# V1_Layout.net
KiCad netlist of a schematic drawn in EAGLE
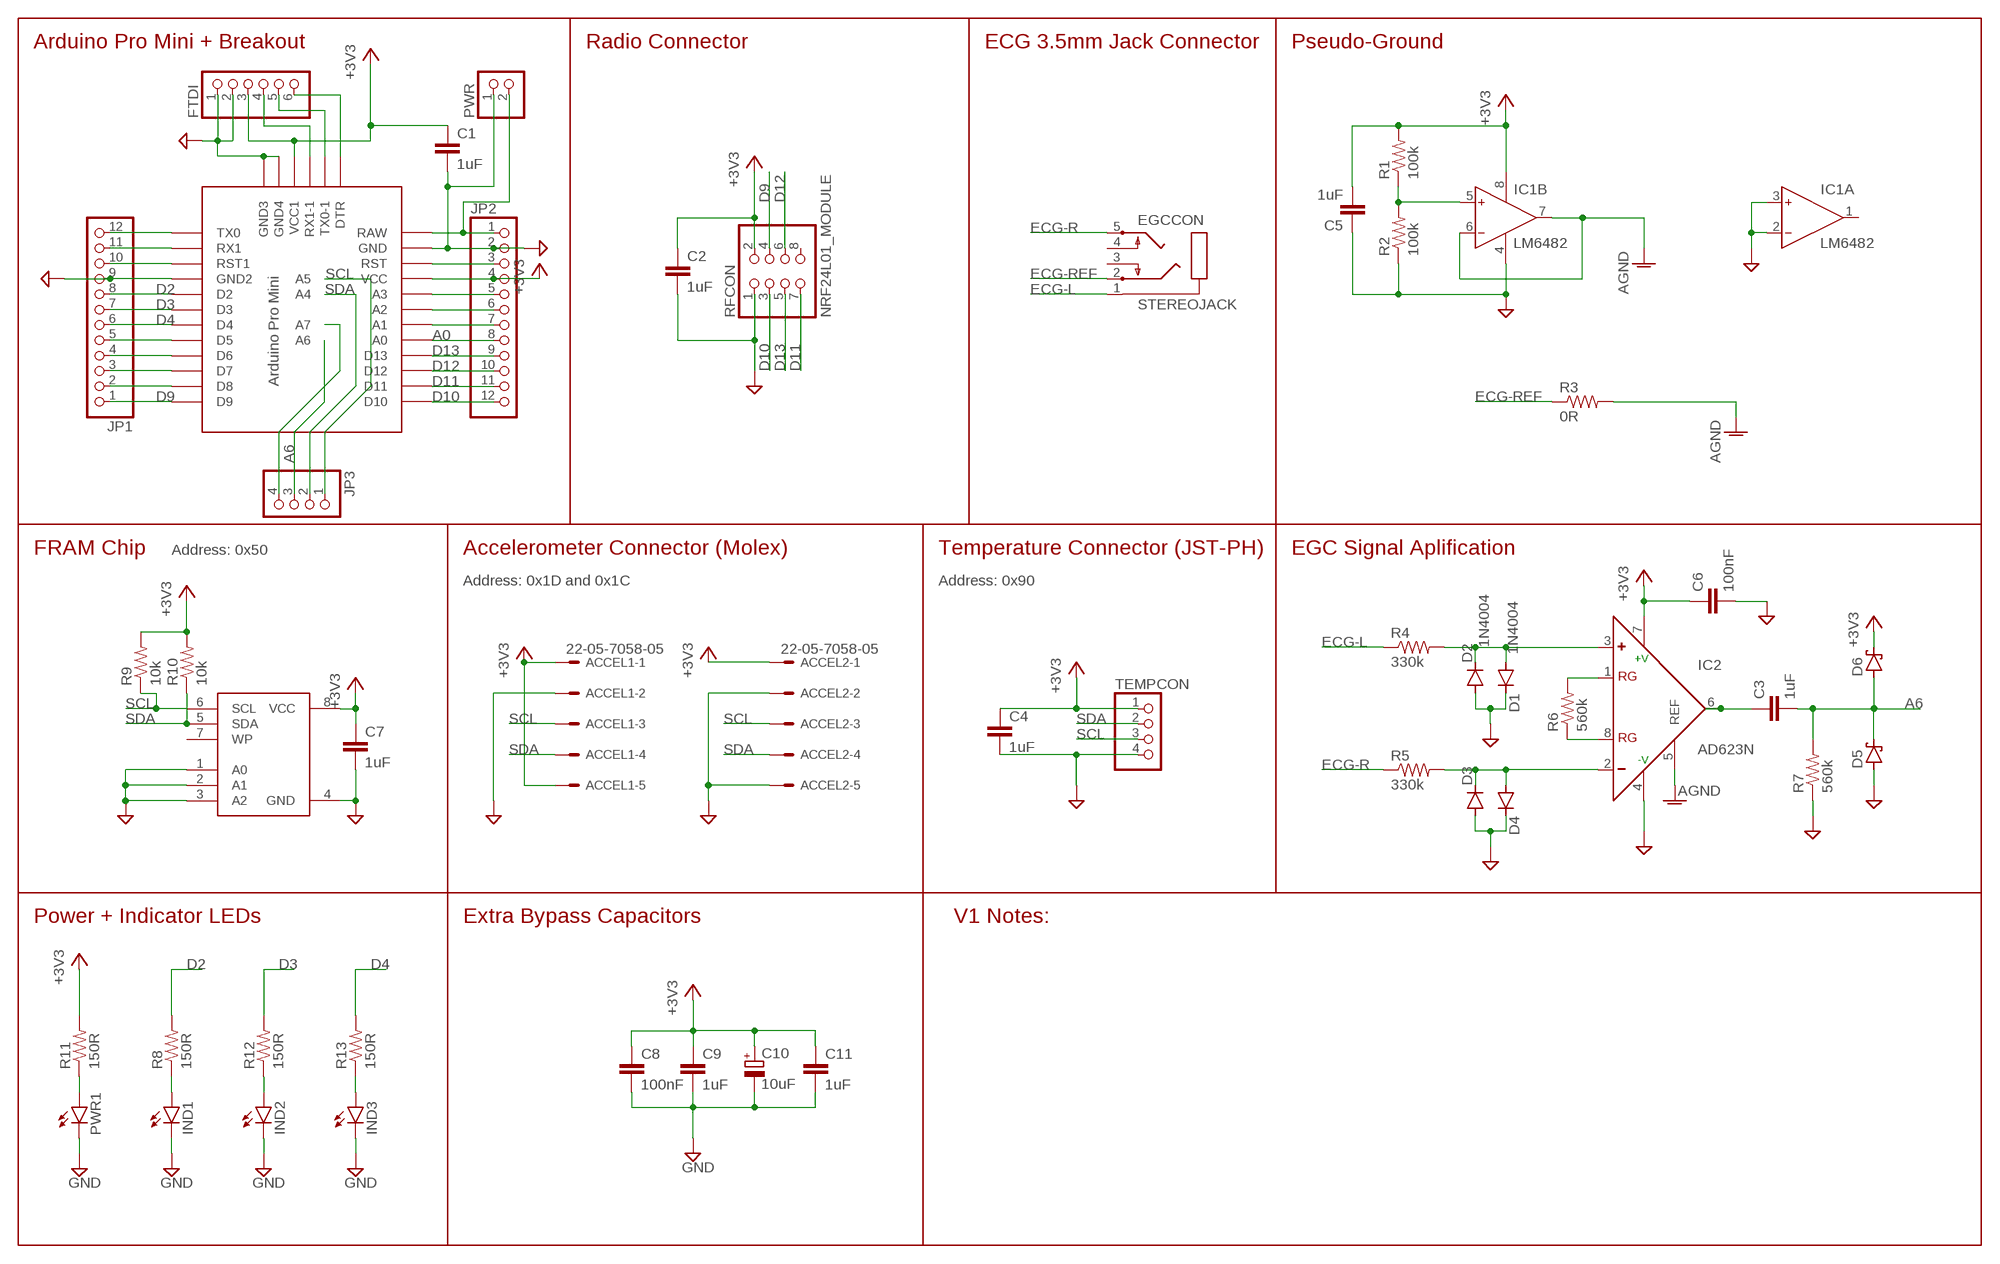
[diagram p0: schematic, sheet 1]

(export (version "E")
  (design (tool "Eeschema 10.0.6"))
  (components
    (comp (ref "ACCEL1")
      (value "22-05-7058-05")
      (footprint "eagle-import:7395-05")
      (fields (field (name "MF") "MOLEX"))
      (libsource (lib "eagle-import") (part "22-?-0505-7058"))
    )
    (comp (ref "ACCEL2")
      (value "22-05-7058-05")
      (footprint "eagle-import:7395-05")
      (fields (field (name "MF") "MOLEX"))
      (libsource (lib "eagle-import") (part "22-?-0505-7058"))
    )
    (comp (ref "C1")
      (value "1uF")
      (footprint "eagle-import:C0603")
      (libsource (lib "eagle-import") (part "C-EUC0603"))
    )
    (comp (ref "C2")
      (value "1uF")
      (footprint "eagle-import:C0603")
      (libsource (lib "eagle-import") (part "C-EUC0603"))
    )
    (comp (ref "C3")
      (value "1uF")
      (footprint "eagle-import:C0603")
      (libsource (lib "eagle-import") (part "C-EUC0603"))
    )
    (comp (ref "C4")
      (value "1uF")
      (footprint "eagle-import:C0603")
      (libsource (lib "eagle-import") (part "C-EUC0603"))
    )
    (comp (ref "C5")
      (value "1uF")
      (footprint "eagle-import:C0603")
      (libsource (lib "eagle-import") (part "C-EUC0603"))
    )
    (comp (ref "C6")
      (value "100nF")
      (footprint "eagle-import:C0603")
      (libsource (lib "eagle-import") (part "C-EUC0603"))
    )
    (comp (ref "C7")
      (value "1uF")
      (footprint "eagle-import:C0603")
      (libsource (lib "eagle-import") (part "C-EUC0603"))
    )
    (comp (ref "C8")
      (value "100nF")
      (footprint "eagle-import:C025-030X050")
      (libsource (lib "eagle-import") (part "C-EU025-030X050"))
    )
    (comp (ref "C9")
      (value "1uF")
      (footprint "eagle-import:C025-030X050")
      (libsource (lib "eagle-import") (part "C-EU025-030X050"))
    )
    (comp (ref "C10")
      (value "10uF")
      (footprint "eagle-import:TAP5-45")
      (libsource (lib "eagle-import") (part "CPOL-EUTAP5-45"))
    )
    (comp (ref "C11")
      (value "1uF")
      (footprint "eagle-import:C025-030X050")
      (libsource (lib "eagle-import") (part "C-EU025-030X050"))
    )
    (comp (ref "D1")
      (value "1N4004")
      (footprint "eagle-import:DO41-10")
      (libsource (lib "eagle-import") (part "1N4004"))
    )
    (comp (ref "D2")
      (value "1N4004")
      (footprint "eagle-import:DO41-10")
      (libsource (lib "eagle-import") (part "1N4004"))
    )
    (comp (ref "D3")
      (value "1N4004")
      (footprint "eagle-import:DO41-10")
      (libsource (lib "eagle-import") (part "1N4004"))
    )
    (comp (ref "D4")
      (value "1N4004")
      (footprint "eagle-import:DO41-10")
      (libsource (lib "eagle-import") (part "1N4004"))
    )
    (comp (ref "D5")
      (value "SCHOTTKY-DIODEDO35-7")
      (footprint "eagle-import:DO35-7")
      (libsource (lib "eagle-import") (part "SCHOTTKY-DIODEDO35-7"))
    )
    (comp (ref "D6")
      (value "SCHOTTKY-DIODEDO35-7")
      (footprint "eagle-import:DO35-7")
      (libsource (lib "eagle-import") (part "SCHOTTKY-DIODEDO35-7"))
    )
    (comp (ref "EGCCON")
      (value "STEREOJACK")
      (footprint "eagle-import:STX3100")
      (libsource (lib "eagle-import") (part "STEREOJACK"))
    )
    (comp (ref "FTDI")
      (value "PINHD-1X6")
      (footprint "eagle-import:1X06")
      (libsource (lib "eagle-import") (part "PINHD-1X6"))
    )
    (comp (ref "IC1")
      (value "LM6482")
      (footprint "eagle-import:DIL08")
      (fields (field (name "MF") "ALTERA CORPORATION") (field (name "MPN") "AD826ANZ"))
      (libsource (lib "eagle-import") (part "AD826N"))
    )
    (comp (ref "IC2")
      (value "AD623N")
      (footprint "eagle-import:DIL08")
      (fields (field (name "MF") "ALTERA CORPORATION") (field (name "MPN") "AD623ANZ"))
      (libsource (lib "eagle-import") (part "AD623N"))
    )
    (comp (ref "IND1")
      (value "LEDCHIPLED_0805")
      (footprint "eagle-import:CHIPLED_0805")
      (libsource (lib "eagle-import") (part "LEDCHIPLED_0805"))
    )
    (comp (ref "IND2")
      (value "LEDCHIPLED_0805")
      (footprint "eagle-import:CHIPLED_0805")
      (libsource (lib "eagle-import") (part "LEDCHIPLED_0805"))
    )
    (comp (ref "IND3")
      (value "LEDCHIPLED_0805")
      (footprint "eagle-import:CHIPLED_0805")
      (libsource (lib "eagle-import") (part "LEDCHIPLED_0805"))
    )
    (comp (ref "JP1")
      (value "PINHD-1X12")
      (footprint "eagle-import:1X12")
      (libsource (lib "eagle-import") (part "PINHD-1X12"))
    )
    (comp (ref "JP2")
      (value "PINHD-1X12")
      (footprint "eagle-import:1X12")
      (libsource (lib "eagle-import") (part "PINHD-1X12"))
    )
    (comp (ref "JP3")
      (value "PINHD-1X4")
      (footprint "eagle-import:1X04")
      (libsource (lib "eagle-import") (part "pinhead_325_PINHD-1X4"))
    )
    (comp (ref "PWR")
      (value "PINHD-1X2")
      (footprint "eagle-import:1X02")
      (libsource (lib "eagle-import") (part "PINHD-1X2"))
    )
    (comp (ref "PWR1")
      (value "LEDCHIPLED_0805")
      (footprint "eagle-import:CHIPLED_0805")
      (libsource (lib "eagle-import") (part "LEDCHIPLED_0805"))
    )
    (comp (ref "R1")
      (value "100k")
      (footprint "eagle-import:R0603")
      (libsource (lib "eagle-import") (part "R-US_R0603"))
    )
    (comp (ref "R2")
      (value "100k")
      (footprint "eagle-import:R0603")
      (libsource (lib "eagle-import") (part "R-US_R0603"))
    )
    (comp (ref "R3")
      (value "0R")
      (footprint "eagle-import:R0603")
      (libsource (lib "eagle-import") (part "R-US_R0603"))
    )
    (comp (ref "R4")
      (value "330k")
      (footprint "eagle-import:R0603")
      (libsource (lib "eagle-import") (part "R-US_R0603"))
    )
    (comp (ref "R5")
      (value "330k")
      (footprint "eagle-import:R0603")
      (libsource (lib "eagle-import") (part "R-US_R0603"))
    )
    (comp (ref "R6")
      (value "560k")
      (footprint "eagle-import:R0603")
      (libsource (lib "eagle-import") (part "R-US_R0603"))
    )
    (comp (ref "R7")
      (value "560k")
      (footprint "eagle-import:R0603")
      (libsource (lib "eagle-import") (part "R-US_R0603"))
    )
    (comp (ref "R8")
      (value "150R")
      (footprint "eagle-import:R0603")
      (libsource (lib "eagle-import") (part "R-US_R0603"))
    )
    (comp (ref "R9")
      (value "10k")
      (footprint "eagle-import:R0603")
      (libsource (lib "eagle-import") (part "R-US_R0603"))
    )
    (comp (ref "R10")
      (value "10k")
      (footprint "eagle-import:R0603")
      (libsource (lib "eagle-import") (part "R-US_R0603"))
    )
    (comp (ref "R11")
      (value "150R")
      (footprint "eagle-import:R0603")
      (libsource (lib "eagle-import") (part "R-US_R0603"))
    )
    (comp (ref "R12")
      (value "150R")
      (footprint "eagle-import:R0603")
      (libsource (lib "eagle-import") (part "R-US_R0603"))
    )
    (comp (ref "R13")
      (value "150R")
      (footprint "eagle-import:R0603")
      (libsource (lib "eagle-import") (part "R-US_R0603"))
    )
    (comp (ref "RFCON")
      (value "NRF24L01_MODULE")
      (footprint "eagle-import:2X04")
      (libsource (lib "eagle-import") (part "NRF24L01_MODULE"))
    )
    (comp (ref "TEMPCON")
      (value "PINHD-1X4M")
      (footprint "eagle-import:1X04M")
      (libsource (lib "eagle-import") (part "PINHD-1X4M"))
    )
    (comp (ref "U$1")
      (value "PRO-MINI-2")
      (footprint "eagle-import:PRO-MINI-2")
      (libsource (lib "eagle-import") (part "PRO-MINI-2"))
    )
    (comp (ref "U2")
      (value "MB85RC256VPF-G-JNERE2")
      (footprint "eagle-import:SOIC8")
      (libsource (lib "eagle-import") (part "MB85RC256VPF-G-JNERE2"))
    )
  )
  (nets
    (net (code "1") (name "+3V3") (class "Default")
      (node (ref "ACCEL1") (pin "1") (pinfunction "S_1") (pintype "passive"))
      (node (ref "ACCEL1") (pin "5") (pinfunction "S_5") (pintype "passive"))
      (node (ref "ACCEL2") (pin "1") (pinfunction "S_1") (pintype "passive"))
      (node (ref "C1") (pin "1") (pinfunction "1_1") (pintype "passive"))
      (node (ref "C10") (pin "+") (pinfunction "+_+") (pintype "passive"))
      (node (ref "C11") (pin "1") (pinfunction "1_1") (pintype "passive"))
      (node (ref "C2") (pin "1") (pinfunction "1_1") (pintype "passive"))
      (node (ref "C4") (pin "1") (pinfunction "1_1") (pintype "passive"))
      (node (ref "C5") (pin "2") (pinfunction "2_2") (pintype "passive"))
      (node (ref "C6") (pin "1") (pinfunction "1_1") (pintype "passive"))
      (node (ref "C7") (pin "1") (pinfunction "1_1") (pintype "passive"))
      (node (ref "C8") (pin "1") (pinfunction "1_1") (pintype "passive"))
      (node (ref "C9") (pin "1") (pinfunction "1_1") (pintype "passive"))
      (node (ref "D6") (pin "C") (pinfunction "C_C") (pintype "passive"))
      (node (ref "FTDI") (pin "3") (pinfunction "3_3") (pintype "passive"))
      (node (ref "IC1") (pin "8") (pinfunction "V+_8") (pintype "power_in"))
      (node (ref "IC2") (pin "7") (pinfunction "+V_7") (pintype "power_in"))
      (node (ref "JP2") (pin "4") (pinfunction "4_4") (pintype "passive"))
      (node (ref "R1") (pin "2") (pinfunction "2_2") (pintype "passive"))
      (node (ref "R10") (pin "2") (pinfunction "2_2") (pintype "passive"))
      (node (ref "R11") (pin "2") (pinfunction "2_2") (pintype "passive"))
      (node (ref "R9") (pin "2") (pinfunction "2_2") (pintype "passive"))
      (node (ref "RFCON") (pin "2") (pinfunction "2_2") (pintype "passive"))
      (node (ref "TEMPCON") (pin "1") (pinfunction "1_1") (pintype "passive"))
      (node (ref "U$1") (pin "VCC") (pinfunction "VCC_VCC") (pintype "bidirectional"))
      (node (ref "U$1") (pin "VCC1") (pinfunction "VCC1_VCC1") (pintype "bidirectional"))
      (node (ref "U2") (pin "8") (pinfunction "VCC_8") (pintype "bidirectional"))
    )
    (net (code "2") (name "/A0") (class "Default")
      (node (ref "JP2") (pin "8") (pinfunction "8_8") (pintype "passive"))
      (node (ref "U$1") (pin "A3") (pinfunction "A0_A3") (pintype "bidirectional"))
    )
    (net (code "3") (name "/A6") (class "Default")
      (node (ref "C3") (pin "2") (pinfunction "2_2") (pintype "passive"))
      (node (ref "D5") (pin "C") (pinfunction "C_C") (pintype "passive"))
      (node (ref "D6") (pin "A") (pinfunction "A_A") (pintype "passive"))
      (node (ref "JP3") (pin "3") (pinfunction "3_3") (pintype "passive"))
      (node (ref "R7") (pin "2") (pinfunction "2_2") (pintype "passive"))
      (node (ref "U$1") (pin "A6") (pinfunction "A6_A6") (pintype "bidirectional"))
    )
    (net (code "4") (name "/D2") (class "Default")
      (node (ref "JP1") (pin "8") (pinfunction "8_8") (pintype "passive"))
      (node (ref "R8") (pin "2") (pinfunction "2_2") (pintype "passive"))
      (node (ref "U$1") (pin "D2") (pinfunction "D2_D2") (pintype "bidirectional"))
    )
    (net (code "5") (name "/D3") (class "Default")
      (node (ref "JP1") (pin "7") (pinfunction "7_7") (pintype "passive"))
      (node (ref "R12") (pin "2") (pinfunction "2_2") (pintype "passive"))
      (node (ref "U$1") (pin "D3") (pinfunction "D3_D3") (pintype "bidirectional"))
    )
    (net (code "6") (name "/D4") (class "Default")
      (node (ref "JP1") (pin "6") (pinfunction "6_6") (pintype "passive"))
      (node (ref "R13") (pin "2") (pinfunction "2_2") (pintype "passive"))
      (node (ref "U$1") (pin "D4") (pinfunction "D4_D4") (pintype "bidirectional"))
    )
    (net (code "7") (name "/D9") (class "Default")
      (node (ref "JP1") (pin "1") (pinfunction "1_1") (pintype "passive"))
      (node (ref "RFCON") (pin "4") (pinfunction "4_4") (pintype "passive"))
      (node (ref "U$1") (pin "D9") (pinfunction "D9_D9") (pintype "bidirectional"))
    )
    (net (code "8") (name "/D10") (class "Default")
      (node (ref "JP2") (pin "12") (pinfunction "12_12") (pintype "passive"))
      (node (ref "RFCON") (pin "3") (pinfunction "3_3") (pintype "passive"))
      (node (ref "U$1") (pin "D10") (pinfunction "D10_D10") (pintype "bidirectional"))
    )
    (net (code "9") (name "/D11") (class "Default")
      (node (ref "JP2") (pin "11") (pinfunction "11_11") (pintype "passive"))
      (node (ref "RFCON") (pin "7") (pinfunction "7_7") (pintype "passive"))
      (node (ref "U$1") (pin "D11") (pinfunction "D11_D11") (pintype "bidirectional"))
    )
    (net (code "10") (name "/D12") (class "Default")
      (node (ref "JP2") (pin "10") (pinfunction "10_10") (pintype "passive"))
      (node (ref "RFCON") (pin "6") (pinfunction "6_6") (pintype "passive"))
      (node (ref "U$1") (pin "D12") (pinfunction "D12_D12") (pintype "bidirectional"))
    )
    (net (code "11") (name "/D13") (class "Default")
      (node (ref "JP2") (pin "9") (pinfunction "9_9") (pintype "passive"))
      (node (ref "RFCON") (pin "5") (pinfunction "5_5") (pintype "passive"))
      (node (ref "U$1") (pin "D13") (pinfunction "D13_D13") (pintype "bidirectional"))
    )
    (net (code "12") (name "/ECG-L") (class "Default")
      (node (ref "EGCCON") (pin "1") (pinfunction "1_1") (pintype "passive"))
      (node (ref "R4") (pin "1") (pinfunction "1_1") (pintype "passive"))
    )
    (net (code "13") (name "/ECG-R") (class "Default")
      (node (ref "EGCCON") (pin "5") (pinfunction "5_5") (pintype "passive"))
      (node (ref "R5") (pin "1") (pinfunction "1_1") (pintype "passive"))
    )
    (net (code "14") (name "/ECG-REF") (class "Default")
      (node (ref "EGCCON") (pin "2") (pinfunction "2_2") (pintype "passive"))
      (node (ref "R3") (pin "1") (pinfunction "1_1") (pintype "passive"))
    )
    (net (code "15") (name "/SCL") (class "Default")
      (node (ref "ACCEL1") (pin "3") (pinfunction "S_3") (pintype "passive"))
      (node (ref "ACCEL2") (pin "3") (pinfunction "S_3") (pintype "passive"))
      (node (ref "JP3") (pin "1") (pinfunction "1_1") (pintype "passive"))
      (node (ref "R9") (pin "1") (pinfunction "1_1") (pintype "passive"))
      (node (ref "TEMPCON") (pin "3") (pinfunction "3_3") (pintype "passive"))
      (node (ref "U$1") (pin "A5") (pinfunction "A5_A5") (pintype "bidirectional"))
      (node (ref "U2") (pin "6") (pinfunction "SCL_6") (pintype "bidirectional"))
    )
    (net (code "16") (name "/SDA") (class "Default")
      (node (ref "ACCEL1") (pin "4") (pinfunction "S_4") (pintype "passive"))
      (node (ref "ACCEL2") (pin "4") (pinfunction "S_4") (pintype "passive"))
      (node (ref "JP3") (pin "2") (pinfunction "2_2") (pintype "passive"))
      (node (ref "R10") (pin "1") (pinfunction "1_1") (pintype "passive"))
      (node (ref "TEMPCON") (pin "2") (pinfunction "2_2") (pintype "passive"))
      (node (ref "U$1") (pin "A4") (pinfunction "A4_A4") (pintype "bidirectional"))
      (node (ref "U2") (pin "5") (pinfunction "SDA_5") (pintype "bidirectional"))
    )
    (net (code "17") (name "AGND") (class "Default")
      (node (ref "IC1") (pin "6") (pinfunction "IN-_6") (pintype "input"))
      (node (ref "IC1") (pin "7") (pinfunction "OUT_7") (pintype "output"))
      (node (ref "IC2") (pin "5") (pinfunction "REF_5") (pintype "passive"))
      (node (ref "R3") (pin "2") (pinfunction "2_2") (pintype "passive"))
    )
    (net (code "18") (name "GND") (class "Default")
      (node (ref "ACCEL1") (pin "2") (pinfunction "S_2") (pintype "passive"))
      (node (ref "ACCEL2") (pin "2") (pinfunction "S_2") (pintype "passive"))
      (node (ref "ACCEL2") (pin "5") (pinfunction "S_5") (pintype "passive"))
      (node (ref "C1") (pin "2") (pinfunction "2_2") (pintype "passive"))
      (node (ref "C10") (pin "-") (pinfunction "-_-") (pintype "passive"))
      (node (ref "C11") (pin "2") (pinfunction "2_2") (pintype "passive"))
      (node (ref "C2") (pin "2") (pinfunction "2_2") (pintype "passive"))
      (node (ref "C4") (pin "2") (pinfunction "2_2") (pintype "passive"))
      (node (ref "C5") (pin "1") (pinfunction "1_1") (pintype "passive"))
      (node (ref "C6") (pin "2") (pinfunction "2_2") (pintype "passive"))
      (node (ref "C7") (pin "2") (pinfunction "2_2") (pintype "passive"))
      (node (ref "C8") (pin "2") (pinfunction "2_2") (pintype "passive"))
      (node (ref "C9") (pin "2") (pinfunction "2_2") (pintype "passive"))
      (node (ref "D1") (pin "C") (pinfunction "C_C") (pintype "passive"))
      (node (ref "D2") (pin "A") (pinfunction "A_A") (pintype "passive"))
      (node (ref "D3") (pin "A") (pinfunction "A_A") (pintype "passive"))
      (node (ref "D4") (pin "C") (pinfunction "C_C") (pintype "passive"))
      (node (ref "D5") (pin "A") (pinfunction "A_A") (pintype "passive"))
      (node (ref "FTDI") (pin "1") (pinfunction "1_1") (pintype "passive"))
      (node (ref "FTDI") (pin "2") (pinfunction "2_2") (pintype "passive"))
      (node (ref "IC1") (pin "2") (pinfunction "IN-_2") (pintype "input"))
      (node (ref "IC1") (pin "3") (pinfunction "IN+_3") (pintype "input"))
      (node (ref "IC1") (pin "4") (pinfunction "V-_4") (pintype "power_in"))
      (node (ref "IC2") (pin "4") (pinfunction "-V_4") (pintype "power_in"))
      (node (ref "IND1") (pin "C") (pinfunction "C_C") (pintype "passive"))
      (node (ref "IND2") (pin "C") (pinfunction "C_C") (pintype "passive"))
      (node (ref "IND3") (pin "C") (pinfunction "C_C") (pintype "passive"))
      (node (ref "JP1") (pin "9") (pinfunction "9_9") (pintype "passive"))
      (node (ref "JP2") (pin "2") (pinfunction "2_2") (pintype "passive"))
      (node (ref "PWR") (pin "1") (pinfunction "1_1") (pintype "passive"))
      (node (ref "PWR1") (pin "C") (pinfunction "C_C") (pintype "passive"))
      (node (ref "R2") (pin "1") (pinfunction "1_1") (pintype "passive"))
      (node (ref "R7") (pin "1") (pinfunction "1_1") (pintype "passive"))
      (node (ref "RFCON") (pin "1") (pinfunction "1_1") (pintype "passive"))
      (node (ref "TEMPCON") (pin "4") (pinfunction "4_4") (pintype "passive"))
      (node (ref "U$1") (pin "GND") (pinfunction "GND_GND") (pintype "bidirectional"))
      (node (ref "U$1") (pin "GND1") (pinfunction "GND2_GND1") (pintype "bidirectional"))
      (node (ref "U$1") (pin "GND2") (pinfunction "GND3_GND2") (pintype "bidirectional"))
      (node (ref "U$1") (pin "GND3") (pinfunction "GND4_GND3") (pintype "bidirectional"))
      (node (ref "U2") (pin "1") (pinfunction "A0_1") (pintype "bidirectional"))
      (node (ref "U2") (pin "2") (pinfunction "A1_2") (pintype "bidirectional"))
      (node (ref "U2") (pin "3") (pinfunction "A2_3") (pintype "bidirectional"))
      (node (ref "U2") (pin "4") (pinfunction "GND_4") (pintype "bidirectional"))
    )
    (net (code "19") (name "Net-(FTDI-Pad4)") (class "Default")
      (node (ref "FTDI") (pin "4") (pinfunction "4_4") (pintype "passive"))
      (node (ref "U$1") (pin "RX1-1") (pinfunction "RX1-1_RX1-1") (pintype "bidirectional"))
    )
    (net (code "20") (name "Net-(FTDI-Pad5)") (class "Default")
      (node (ref "FTDI") (pin "5") (pinfunction "5_5") (pintype "passive"))
      (node (ref "U$1") (pin "TX0-1") (pinfunction "TX0-1_TX0-1") (pintype "bidirectional"))
    )
    (net (code "21") (name "Net-(FTDI-Pad6)") (class "Default")
      (node (ref "FTDI") (pin "6") (pinfunction "6_6") (pintype "passive"))
      (node (ref "U$1") (pin "DTR") (pinfunction "DTR_DTR") (pintype "bidirectional"))
    )
    (net (code "22") (name "Net-(IC1B-IN+)") (class "Default")
      (node (ref "IC1") (pin "5") (pinfunction "IN+_5") (pintype "input"))
      (node (ref "R1") (pin "1") (pinfunction "1_1") (pintype "passive"))
      (node (ref "R2") (pin "2") (pinfunction "2_2") (pintype "passive"))
    )
    (net (code "23") (name "Net-(IC2-+)") (class "Default")
      (node (ref "D1") (pin "A") (pinfunction "A_A") (pintype "passive"))
      (node (ref "D2") (pin "C") (pinfunction "C_C") (pintype "passive"))
      (node (ref "IC2") (pin "3") (pinfunction "+_3") (pintype "input"))
      (node (ref "R4") (pin "2") (pinfunction "2_2") (pintype "passive"))
    )
    (net (code "24") (name "Net-(IC2--)") (class "Default")
      (node (ref "D3") (pin "C") (pinfunction "C_C") (pintype "passive"))
      (node (ref "D4") (pin "A") (pinfunction "A_A") (pintype "passive"))
      (node (ref "IC2") (pin "2") (pinfunction "-_2") (pintype "input"))
      (node (ref "R5") (pin "2") (pinfunction "2_2") (pintype "passive"))
    )
    (net (code "25") (name "Net-(IC2-OUT)") (class "Default")
      (node (ref "C3") (pin "1") (pinfunction "1_1") (pintype "passive"))
      (node (ref "IC2") (pin "6") (pinfunction "OUT_6") (pintype "output"))
    )
    (net (code "26") (name "Net-(IC2-RG-Pad1)") (class "Default")
      (node (ref "IC2") (pin "1") (pinfunction "RG_1") (pintype "passive"))
      (node (ref "R6") (pin "2") (pinfunction "2_2") (pintype "passive"))
    )
    (net (code "27") (name "Net-(IC2-RG-Pad8)") (class "Default")
      (node (ref "IC2") (pin "8") (pinfunction "RG_8") (pintype "passive"))
      (node (ref "R6") (pin "1") (pinfunction "1_1") (pintype "passive"))
    )
    (net (code "28") (name "Net-(IND1-PadA)") (class "Default")
      (node (ref "IND1") (pin "A") (pinfunction "A_A") (pintype "passive"))
      (node (ref "R8") (pin "1") (pinfunction "1_1") (pintype "passive"))
    )
    (net (code "29") (name "Net-(IND2-PadA)") (class "Default")
      (node (ref "IND2") (pin "A") (pinfunction "A_A") (pintype "passive"))
      (node (ref "R12") (pin "1") (pinfunction "1_1") (pintype "passive"))
    )
    (net (code "30") (name "Net-(IND3-PadA)") (class "Default")
      (node (ref "IND3") (pin "A") (pinfunction "A_A") (pintype "passive"))
      (node (ref "R13") (pin "1") (pinfunction "1_1") (pintype "passive"))
    )
    (net (code "31") (name "Net-(JP1-Pad2)") (class "Default")
      (node (ref "JP1") (pin "2") (pinfunction "2_2") (pintype "passive"))
      (node (ref "U$1") (pin "D8") (pinfunction "D8_D8") (pintype "bidirectional"))
    )
    (net (code "32") (name "Net-(JP1-Pad3)") (class "Default")
      (node (ref "JP1") (pin "3") (pinfunction "3_3") (pintype "passive"))
      (node (ref "U$1") (pin "D7") (pinfunction "D7_D7") (pintype "bidirectional"))
    )
    (net (code "33") (name "Net-(JP1-Pad4)") (class "Default")
      (node (ref "JP1") (pin "4") (pinfunction "4_4") (pintype "passive"))
      (node (ref "U$1") (pin "D6") (pinfunction "D6_D6") (pintype "bidirectional"))
    )
    (net (code "34") (name "Net-(JP1-Pad5)") (class "Default")
      (node (ref "JP1") (pin "5") (pinfunction "5_5") (pintype "passive"))
      (node (ref "U$1") (pin "D5") (pinfunction "D5_D5") (pintype "bidirectional"))
    )
    (net (code "35") (name "Net-(JP1-Pad10)") (class "Default")
      (node (ref "JP1") (pin "10") (pinfunction "10_10") (pintype "passive"))
      (node (ref "U$1") (pin "RST1") (pinfunction "RST1_RST1") (pintype "bidirectional"))
    )
    (net (code "36") (name "Net-(JP1-Pad11)") (class "Default")
      (node (ref "JP1") (pin "11") (pinfunction "11_11") (pintype "passive"))
      (node (ref "U$1") (pin "RX1") (pinfunction "RX1_RX1") (pintype "bidirectional"))
    )
    (net (code "37") (name "Net-(JP1-Pad12)") (class "Default")
      (node (ref "JP1") (pin "12") (pinfunction "12_12") (pintype "passive"))
      (node (ref "U$1") (pin "TX0") (pinfunction "TX0_TX0") (pintype "bidirectional"))
    )
    (net (code "38") (name "Net-(JP2-Pad1)") (class "Default")
      (node (ref "JP2") (pin "1") (pinfunction "1_1") (pintype "passive"))
      (node (ref "PWR") (pin "2") (pinfunction "2_2") (pintype "passive"))
      (node (ref "U$1") (pin "RAW") (pinfunction "RAW_RAW") (pintype "bidirectional"))
    )
    (net (code "39") (name "Net-(JP2-Pad3)") (class "Default")
      (node (ref "JP2") (pin "3") (pinfunction "3_3") (pintype "passive"))
      (node (ref "U$1") (pin "RST") (pinfunction "RST_RST") (pintype "bidirectional"))
    )
    (net (code "40") (name "Net-(JP3-Pad4)") (class "Default")
      (node (ref "JP3") (pin "4") (pinfunction "4_4") (pintype "passive"))
      (node (ref "U$1") (pin "A7") (pinfunction "A7_A7") (pintype "bidirectional"))
    )
    (net (code "41") (name "Net-(PWR1-PadA)") (class "Default")
      (node (ref "PWR1") (pin "A") (pinfunction "A_A") (pintype "passive"))
      (node (ref "R11") (pin "1") (pinfunction "1_1") (pintype "passive"))
    )
    (net (code "42") (name "Net-(U$1-A1)") (class "Default")
      (node (ref "JP2") (pin "7") (pinfunction "7_7") (pintype "passive"))
      (node (ref "U$1") (pin "A2") (pinfunction "A1_A2") (pintype "bidirectional"))
    )
    (net (code "43") (name "Net-(U$1-A2)") (class "Default")
      (node (ref "JP2") (pin "6") (pinfunction "6_6") (pintype "passive"))
      (node (ref "U$1") (pin "A1") (pinfunction "A2_A1") (pintype "bidirectional"))
    )
    (net (code "44") (name "Net-(U$1-A3)") (class "Default")
      (node (ref "JP2") (pin "5") (pinfunction "5_5") (pintype "passive"))
      (node (ref "U$1") (pin "A0") (pinfunction "A3_A0") (pintype "bidirectional"))
    )
    (net (code "45") (name "unconnected-(EGCCON-Pad3)") (class "Default")
      (node (ref "EGCCON") (pin "3") (pinfunction "3_3") (pintype "passive"))
    )
    (net (code "46") (name "unconnected-(EGCCON-Pad4)") (class "Default")
      (node (ref "EGCCON") (pin "4") (pinfunction "4_4") (pintype "passive"))
    )
    (net (code "47") (name "unconnected-(IC1A-OUT-Pad1)") (class "Default")
      (node (ref "IC1") (pin "1") (pinfunction "OUT_1") (pintype "output"))
    )
    (net (code "48") (name "unconnected-(RFCON-Pad8)") (class "Default")
      (node (ref "RFCON") (pin "8") (pinfunction "8_8") (pintype "passive"))
    )
    (net (code "49") (name "unconnected-(U2-WP-Pad7)") (class "Default")
      (node (ref "U2") (pin "7") (pinfunction "WP_7") (pintype "bidirectional"))
    )
  )
)
